# PhMeter_1.net
KiCad netlist of a schematic drawn in EAGLE
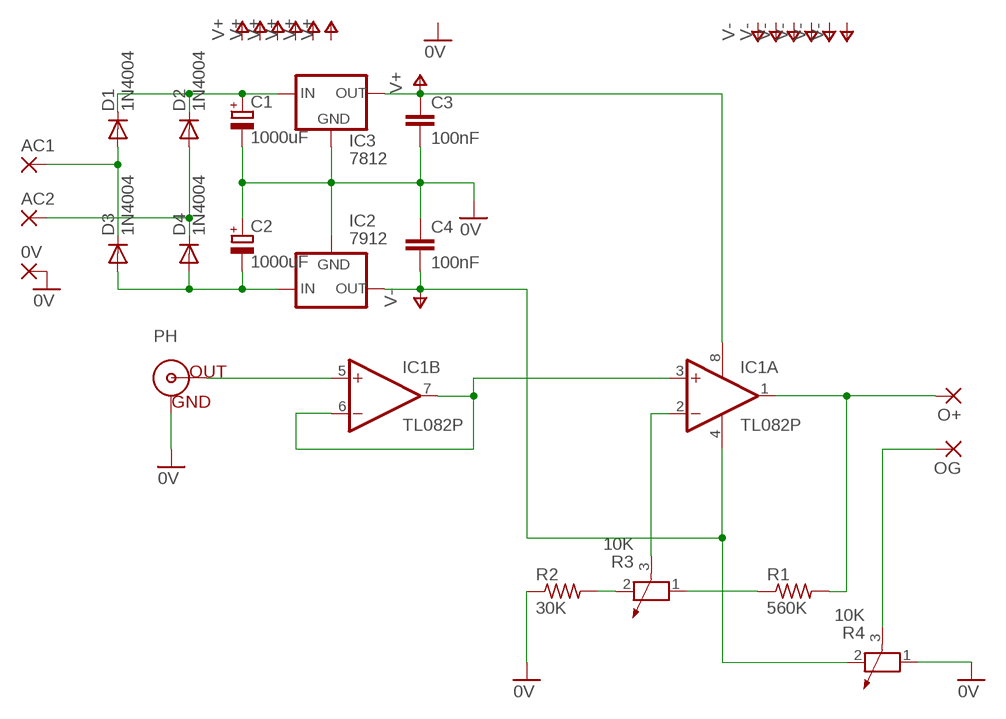
[diagram p0: schematic, sheet 1]

(export (version "E")
  (design (tool "Eeschema 10.0.6"))
  (components
    (comp (ref "0V")
      (value "1,6/0,8")
      (footprint "eagle-import:1,6_0,8")
      (libsource (lib "eagle-import") (part "1,6/0,8"))
    )
    (comp (ref "AC1")
      (value "1,6/0,8")
      (footprint "eagle-import:1,6_0,8")
      (libsource (lib "eagle-import") (part "1,6/0,8"))
    )
    (comp (ref "AC2")
      (value "1,6/0,8")
      (footprint "eagle-import:1,6_0,8")
      (libsource (lib "eagle-import") (part "1,6/0,8"))
    )
    (comp (ref "C1")
      (value "1000uF")
      (footprint "eagle-import:E7,5-18")
      (libsource (lib "eagle-import") (part "CPOL-EUE7.5-18"))
    )
    (comp (ref "C2")
      (value "1000uF")
      (footprint "eagle-import:E7,5-18")
      (libsource (lib "eagle-import") (part "CPOL-EUE7.5-18"))
    )
    (comp (ref "C3")
      (value "100nF")
      (footprint "eagle-import:C050-025X075")
      (libsource (lib "eagle-import") (part "C-EU050-025X075"))
    )
    (comp (ref "C4")
      (value "100nF")
      (footprint "eagle-import:C050-025X075")
      (libsource (lib "eagle-import") (part "C-EU050-025X075"))
    )
    (comp (ref "D1")
      (value "1N4004")
      (footprint "eagle-import:DO41-10")
      (libsource (lib "eagle-import") (part "1N4004"))
    )
    (comp (ref "D2")
      (value "1N4004")
      (footprint "eagle-import:DO41-10")
      (libsource (lib "eagle-import") (part "1N4004"))
    )
    (comp (ref "D3")
      (value "1N4004")
      (footprint "eagle-import:DO41-10")
      (libsource (lib "eagle-import") (part "1N4004"))
    )
    (comp (ref "D4")
      (value "1N4004")
      (footprint "eagle-import:DO41-10")
      (libsource (lib "eagle-import") (part "1N4004"))
    )
    (comp (ref "IC1")
      (value "TL082P")
      (footprint "eagle-import:DIL08")
      (libsource (lib "eagle-import") (part "TL082P"))
    )
    (comp (ref "IC2")
      (value "7912")
      (footprint "eagle-import:79XXS")
      (libsource (lib "eagle-import") (part "79XXS"))
    )
    (comp (ref "IC3")
      (value "7812")
      (footprint "eagle-import:78XXS")
      (libsource (lib "eagle-import") (part "78XXS"))
    )
    (comp (ref "O+")
      (value "1,6/0,8")
      (footprint "eagle-import:1,6_0,8")
      (libsource (lib "eagle-import") (part "1,6/0,8"))
    )
    (comp (ref "OG")
      (value "1,6/0,8")
      (footprint "eagle-import:1,6_0,8")
      (libsource (lib "eagle-import") (part "1,6/0,8"))
    )
    (comp (ref "PH")
      (value "BNCPTH")
      (footprint "eagle-import:BNC")
      (libsource (lib "eagle-import") (part "BNCPTH"))
    )
    (comp (ref "R1")
      (value "560K")
      (footprint "eagle-import:0207_10")
      (libsource (lib "eagle-import") (part "R-US_0207/10"))
    )
    (comp (ref "R2")
      (value "30K")
      (footprint "eagle-import:0207_10")
      (libsource (lib "eagle-import") (part "R-US_0207/10"))
    )
    (comp (ref "R3")
      (value "10K")
      (footprint "eagle-import:PT-10")
      (libsource (lib "eagle-import") (part "POTENTIOMETER_PT-10"))
    )
    (comp (ref "R4")
      (value "10K")
      (footprint "eagle-import:PT-10")
      (libsource (lib "eagle-import") (part "POTENTIOMETER_PT-10"))
    )
  )
  (nets
    (net (code "1") (name "0V") (class "Default")
      (node (ref "0V") (pin "1") (pinfunction "P_1") (pintype "passive"))
      (node (ref "C1") (pin "-") (pinfunction "-_-") (pintype "passive"))
      (node (ref "C2") (pin "+") (pinfunction "+_+") (pintype "passive"))
      (node (ref "C3") (pin "2") (pinfunction "2_2") (pintype "passive"))
      (node (ref "C4") (pin "1") (pinfunction "1_1") (pintype "passive"))
      (node (ref "IC2") (pin "GND") (pinfunction "GND_GND") (pintype "input"))
      (node (ref "IC3") (pin "GND") (pinfunction "GND_GND") (pintype "input"))
      (node (ref "PH") (pin "GND") (pinfunction "GND_GND") (pintype "bidirectional"))
      (node (ref "R2") (pin "1") (pinfunction "1_1") (pintype "passive"))
      (node (ref "R4") (pin "1") (pinfunction "1_1") (pintype "passive"))
    )
    (net (code "2") (name "Net-(AC1-P)") (class "Default")
      (node (ref "AC1") (pin "1") (pinfunction "P_1") (pintype "passive"))
      (node (ref "D1") (pin "A") (pinfunction "A_A") (pintype "passive"))
      (node (ref "D3") (pin "C") (pinfunction "C_C") (pintype "passive"))
    )
    (net (code "3") (name "Net-(AC2-P)") (class "Default")
      (node (ref "AC2") (pin "1") (pinfunction "P_1") (pintype "passive"))
      (node (ref "D2") (pin "A") (pinfunction "A_A") (pintype "passive"))
      (node (ref "D4") (pin "C") (pinfunction "C_C") (pintype "passive"))
    )
    (net (code "4") (name "Net-(C1-Pad+)") (class "Default")
      (node (ref "C1") (pin "+") (pinfunction "+_+") (pintype "passive"))
      (node (ref "D1") (pin "C") (pinfunction "C_C") (pintype "passive"))
      (node (ref "D2") (pin "C") (pinfunction "C_C") (pintype "passive"))
      (node (ref "IC3") (pin "IN") (pinfunction "IN_IN") (pintype "input"))
    )
    (net (code "5") (name "Net-(C2-Pad-)") (class "Default")
      (node (ref "C2") (pin "-") (pinfunction "-_-") (pintype "passive"))
      (node (ref "D3") (pin "A") (pinfunction "A_A") (pintype "passive"))
      (node (ref "D4") (pin "A") (pinfunction "A_A") (pintype "passive"))
      (node (ref "IC2") (pin "IN") (pinfunction "IN_IN") (pintype "input"))
    )
    (net (code "6") (name "Net-(IC1A-+IN)") (class "Default")
      (node (ref "IC1") (pin "3") (pinfunction "+IN_3") (pintype "input"))
      (node (ref "IC1") (pin "6") (pinfunction "-IN_6") (pintype "input"))
      (node (ref "IC1") (pin "7") (pinfunction "OUT_7") (pintype "output"))
    )
    (net (code "7") (name "Net-(IC1A--IN)") (class "Default")
      (node (ref "IC1") (pin "2") (pinfunction "-IN_2") (pintype "input"))
      (node (ref "R3") (pin "3") (pinfunction "3_3") (pintype "passive"))
    )
    (net (code "8") (name "Net-(IC1A-OUT)") (class "Default")
      (node (ref "IC1") (pin "1") (pinfunction "OUT_1") (pintype "output"))
      (node (ref "O+") (pin "1") (pinfunction "P_1") (pintype "passive"))
      (node (ref "R1") (pin "2") (pinfunction "2_2") (pintype "passive"))
    )
    (net (code "9") (name "Net-(IC1B-+IN)") (class "Default")
      (node (ref "IC1") (pin "5") (pinfunction "+IN_5") (pintype "input"))
      (node (ref "PH") (pin "S") (pinfunction "OUT_S") (pintype "bidirectional"))
    )
    (net (code "10") (name "Net-(OG-P)") (class "Default")
      (node (ref "OG") (pin "1") (pinfunction "P_1") (pintype "passive"))
      (node (ref "R4") (pin "3") (pinfunction "3_3") (pintype "passive"))
    )
    (net (code "11") (name "Net-(R1-Pad1)") (class "Default")
      (node (ref "R1") (pin "1") (pinfunction "1_1") (pintype "passive"))
      (node (ref "R3") (pin "1") (pinfunction "1_1") (pintype "passive"))
    )
    (net (code "12") (name "Net-(R2-Pad2)") (class "Default")
      (node (ref "R2") (pin "2") (pinfunction "2_2") (pintype "passive"))
      (node (ref "R3") (pin "2") (pinfunction "2_2") (pintype "passive"))
    )
    (net (code "13") (name "V+") (class "Default")
      (node (ref "C3") (pin "1") (pinfunction "1_1") (pintype "passive"))
      (node (ref "IC1") (pin "8") (pinfunction "V+_8") (pintype "power_in"))
      (node (ref "IC3") (pin "OUT") (pinfunction "OUT_OUT") (pintype "passive"))
    )
    (net (code "14") (name "V-") (class "Default")
      (node (ref "C4") (pin "2") (pinfunction "2_2") (pintype "passive"))
      (node (ref "IC1") (pin "4") (pinfunction "V-_4") (pintype "power_in"))
      (node (ref "IC2") (pin "OUT") (pinfunction "OUT_OUT") (pintype "passive"))
      (node (ref "R4") (pin "2") (pinfunction "2_2") (pintype "passive"))
    )
  )
)
